# ZLS-027.net
KiCad netlist of a schematic drawn in Altium Designer
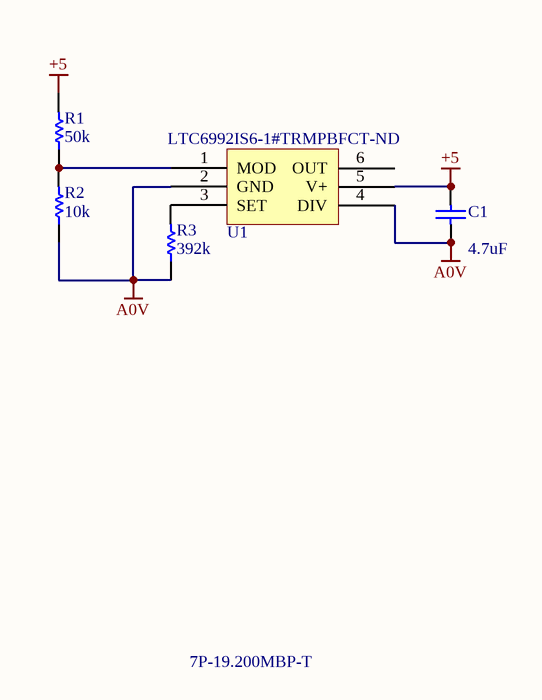
[diagram p0: ZLS-027.SchDoc]

(export (version "E")
  (design (tool "Eeschema 10.0.6"))
  (components
    (comp (ref "C1")
      (value "4.7uF")
      (footprint "CAPC1206(3216)110_N")
      (libsource (lib "Altium Content Vault") (part "CMP-1037-04332-1"))
    )
    (comp (ref "R1")
      (value "RES SMD 43K OHM 1% 1/8W 0805")
      (footprint "RESC0805(2012)_M")
      (description "RES SMD 10K OHM 1% 1/8W 0805")
      (fields (field (name "RESISTANCE (OHMS)") "50k"))
      (libsource (lib "Altium Content Vault") (part "CMP-1013-00017-1"))
    )
    (comp (ref "R2")
      (value "RES SMD 43K OHM 1% 1/8W 0805")
      (footprint "RESC0805(2012)_M")
      (description "RES SMD 10K OHM 1% 1/8W 0805")
      (fields (field (name "RESISTANCE (OHMS)") "10k"))
      (libsource (lib "Altium Content Vault") (part "CMP-1013-00017-1"))
    )
    (comp (ref "R3")
      (value "RES SMD 43K OHM 1% 1/8W 0805")
      (footprint "RESC0805(2012)_M")
      (description "RES SMD 10K OHM 1% 1/8W 0805")
      (fields (field (name "RESISTANCE (OHMS)") "392k"))
      (libsource (lib "Altium Content Vault") (part "CMP-1013-00017-1"))
    )
    (comp (ref "U1")
      (value "LTC6992")
      (footprint "SOT95P280X445-6N")
      (description "IC OSC SILICON PROG TSOT23-6")
      (fields
        (field (name "SUPPLIER PART NUMBER 1") "LTC6992IS6-1#TRMPBFCT-ND")
        (field (name "MANUFACTURER") "Linear Technology/Analog Devices")
        (field (name "MANUFACTURER PART NUMBER") "LTC6992IS6-1#TRMPBF")
      )
      (libsource (lib "ZLS_Schematic_lib") (part "LTC6992"))
    )
  )
  (nets
    (net (code "1") (name "+5") (class "Default")
      (node (ref "C1") (pin "2") (pinfunction "2_2") (pintype "passive"))
      (node (ref "R1") (pin "2") (pinfunction "2_2") (pintype "passive"))
      (node (ref "U1") (pin "5") (pinfunction "V+_5") (pintype "passive"))
    )
    (net (code "2") (name "A0V") (class "Default")
      (node (ref "C1") (pin "1") (pinfunction "1_1") (pintype "passive"))
      (node (ref "R2") (pin "1") (pinfunction "1_1") (pintype "passive"))
      (node (ref "R3") (pin "1") (pinfunction "1_1") (pintype "passive"))
      (node (ref "U1") (pin "2") (pinfunction "GND_2") (pintype "passive"))
      (node (ref "U1") (pin "4") (pinfunction "DIV_4") (pintype "passive"))
    )
    (net (code "3") (name "Net-(U1-MOD)") (class "Default")
      (node (ref "R1") (pin "1") (pinfunction "1_1") (pintype "passive"))
      (node (ref "R2") (pin "2") (pinfunction "2_2") (pintype "passive"))
      (node (ref "U1") (pin "1") (pinfunction "MOD_1") (pintype "passive"))
    )
    (net (code "4") (name "Net-(U1-SET)") (class "Default")
      (node (ref "R3") (pin "2") (pinfunction "2_2") (pintype "passive"))
      (node (ref "U1") (pin "3") (pinfunction "SET_3") (pintype "passive"))
    )
    (net (code "5") (name "unconnected-(U1-OUT-Pad6)") (class "Default")
      (node (ref "U1") (pin "6") (pinfunction "OUT_6") (pintype "passive"))
    )
  )
)
